# capstone_electrical_circuit_rev3.net
KiCad netlist of a schematic drawn in EAGLE
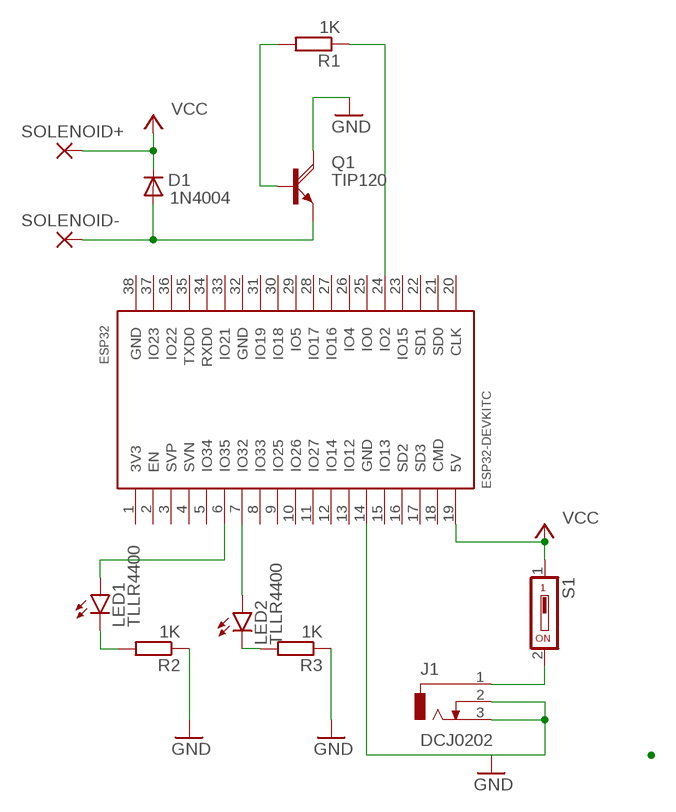
[diagram p0: schematic, sheet 1]

(export (version "E")
  (design (tool "Eeschema 10.0.6"))
  (components
    (comp (ref "D1")
      (value "1N4004")
      (footprint "eagle-import:DO41-10")
      (libsource (lib "eagle-import") (part "1N4004"))
    )
    (comp (ref "ESP32")
      (value "ESP32DEVKITC")
      (footprint "eagle-import:ESP32-DEVKITC")
      (libsource (lib "eagle-import") (part "ESP32DEVKITC"))
    )
    (comp (ref "J1")
      (value "DCJ0202")
      (footprint "eagle-import:DCJ0202")
      (libsource (lib "eagle-import") (part "DCJ0202"))
    )
    (comp (ref "LED1")
      (value "TLLR4400")
      (footprint "eagle-import:LED3MM")
      (fields (field (name "MF") "VISHAY SEMICONDUCTOR"))
      (libsource (lib "eagle-import") (part "TLLR4400"))
    )
    (comp (ref "LED2")
      (value "TLLR4400")
      (footprint "eagle-import:LED3MM")
      (fields (field (name "MF") "VISHAY SEMICONDUCTOR"))
      (libsource (lib "eagle-import") (part "TLLR4400"))
    )
    (comp (ref "Q1")
      (value "TIP120")
      (footprint "eagle-import:TO220AH")
      (libsource (lib "eagle-import") (part "TIP120"))
    )
    (comp (ref "R1")
      (value "1K")
      (footprint "eagle-import:0207_10")
      (libsource (lib "eagle-import") (part "R-EU_0207/10"))
    )
    (comp (ref "R2")
      (value "1K")
      (footprint "eagle-import:0207_10")
      (libsource (lib "eagle-import") (part "R-EU_0207/10"))
    )
    (comp (ref "R3")
      (value "1K")
      (footprint "eagle-import:0207_10")
      (libsource (lib "eagle-import") (part "R-EU_0207/10"))
    )
    (comp (ref "S1")
      (value "SD4-01")
      (footprint "eagle-import:SD4-01")
      (libsource (lib "eagle-import") (part "SD4-01"))
    )
    (comp (ref "SOLENOID+")
      (value "WIREPAD2,54/1,0")
      (footprint "eagle-import:2,54_1,0")
      (libsource (lib "eagle-import") (part "WIREPAD2,54/1,0"))
    )
    (comp (ref "SOLENOID-")
      (value "WIREPAD2,54/1,0")
      (footprint "eagle-import:2,54_1,0")
      (libsource (lib "eagle-import") (part "WIREPAD2,54/1,0"))
    )
  )
  (nets
    (net (code "1") (name "GND") (class "Default")
      (node (ref "ESP32") (pin "14") (pinfunction "GND_14") (pintype "bidirectional"))
      (node (ref "J1") (pin "2") (pinfunction "2_2") (pintype "passive"))
      (node (ref "J1") (pin "3") (pinfunction "3_3") (pintype "passive"))
      (node (ref "Q1") (pin "C") (pinfunction "C_C") (pintype "passive"))
      (node (ref "R2") (pin "1") (pinfunction "1_1") (pintype "passive"))
      (node (ref "R3") (pin "1") (pinfunction "1_1") (pintype "passive"))
    )
    (net (code "2") (name "Net-(ESP32-IO2)") (class "Default")
      (node (ref "ESP32") (pin "24") (pinfunction "IO2_24") (pintype "bidirectional"))
      (node (ref "R1") (pin "1") (pinfunction "1_1") (pintype "passive"))
    )
    (net (code "3") (name "Net-(ESP32-IO32)") (class "Default")
      (node (ref "ESP32") (pin "7") (pinfunction "IO32_7") (pintype "bidirectional"))
      (node (ref "LED2") (pin "A") (pinfunction "A_A") (pintype "passive"))
    )
    (net (code "4") (name "Net-(ESP32-IO35)") (class "Default")
      (node (ref "ESP32") (pin "6") (pinfunction "IO35_6") (pintype "bidirectional"))
      (node (ref "LED1") (pin "A") (pinfunction "A_A") (pintype "passive"))
    )
    (net (code "5") (name "Net-(J1-Pad1)") (class "Default")
      (node (ref "J1") (pin "1") (pinfunction "1_1") (pintype "passive"))
      (node (ref "S1") (pin "2") (pinfunction "2_2") (pintype "passive"))
    )
    (net (code "6") (name "Net-(LED1-C)") (class "Default")
      (node (ref "LED1") (pin "K") (pinfunction "C_K") (pintype "passive"))
      (node (ref "R2") (pin "2") (pinfunction "2_2") (pintype "passive"))
    )
    (net (code "7") (name "Net-(LED2-C)") (class "Default")
      (node (ref "LED2") (pin "K") (pinfunction "C_K") (pintype "passive"))
      (node (ref "R3") (pin "2") (pinfunction "2_2") (pintype "passive"))
    )
    (net (code "8") (name "Net-(Q1-PadB)") (class "Default")
      (node (ref "Q1") (pin "B") (pinfunction "B_B") (pintype "passive"))
      (node (ref "R1") (pin "2") (pinfunction "2_2") (pintype "passive"))
    )
    (net (code "9") (name "Net-(SOLENOID--P)") (class "Default")
      (node (ref "D1") (pin "A") (pinfunction "A_A") (pintype "passive"))
      (node (ref "Q1") (pin "E") (pinfunction "E_E") (pintype "passive"))
      (node (ref "SOLENOID-") (pin "1") (pinfunction "P_1") (pintype "passive"))
    )
    (net (code "10") (name "VCC") (class "Default")
      (node (ref "D1") (pin "C") (pinfunction "C_C") (pintype "passive"))
      (node (ref "ESP32") (pin "19") (pinfunction "5V_19") (pintype "bidirectional"))
      (node (ref "S1") (pin "1") (pinfunction "1_1") (pintype "passive"))
      (node (ref "SOLENOID+") (pin "1") (pinfunction "P_1") (pintype "passive"))
    )
    (net (code "11") (name "unconnected-(ESP32-3V3-Pad1)") (class "Default")
      (node (ref "ESP32") (pin "1") (pinfunction "3V3_1") (pintype "bidirectional"))
    )
    (net (code "12") (name "unconnected-(ESP32-CLK-Pad20)") (class "Default")
      (node (ref "ESP32") (pin "20") (pinfunction "CLK_20") (pintype "bidirectional"))
    )
    (net (code "13") (name "unconnected-(ESP32-CMD-Pad18)") (class "Default")
      (node (ref "ESP32") (pin "18") (pinfunction "CMD_18") (pintype "bidirectional"))
    )
    (net (code "14") (name "unconnected-(ESP32-EN-Pad2)") (class "Default")
      (node (ref "ESP32") (pin "2") (pinfunction "EN_2") (pintype "bidirectional"))
    )
    (net (code "15") (name "unconnected-(ESP32-GND-Pad32)") (class "Default")
      (node (ref "ESP32") (pin "32") (pinfunction "GND_32") (pintype "bidirectional"))
    )
    (net (code "16") (name "unconnected-(ESP32-GND-Pad38)") (class "Default")
      (node (ref "ESP32") (pin "38") (pinfunction "GND_38") (pintype "bidirectional"))
    )
    (net (code "17") (name "unconnected-(ESP32-IO0-Pad25)") (class "Default")
      (node (ref "ESP32") (pin "25") (pinfunction "IO0_25") (pintype "bidirectional"))
    )
    (net (code "18") (name "unconnected-(ESP32-IO4-Pad26)") (class "Default")
      (node (ref "ESP32") (pin "26") (pinfunction "IO4_26") (pintype "bidirectional"))
    )
    (net (code "19") (name "unconnected-(ESP32-IO5-Pad29)") (class "Default")
      (node (ref "ESP32") (pin "29") (pinfunction "IO5_29") (pintype "bidirectional"))
    )
    (net (code "20") (name "unconnected-(ESP32-IO12-Pad13)") (class "Default")
      (node (ref "ESP32") (pin "13") (pinfunction "IO12_13") (pintype "bidirectional"))
    )
    (net (code "21") (name "unconnected-(ESP32-IO13-Pad15)") (class "Default")
      (node (ref "ESP32") (pin "15") (pinfunction "IO13_15") (pintype "bidirectional"))
    )
    (net (code "22") (name "unconnected-(ESP32-IO14-Pad12)") (class "Default")
      (node (ref "ESP32") (pin "12") (pinfunction "IO14_12") (pintype "bidirectional"))
    )
    (net (code "23") (name "unconnected-(ESP32-IO15-Pad23)") (class "Default")
      (node (ref "ESP32") (pin "23") (pinfunction "IO15_23") (pintype "bidirectional"))
    )
    (net (code "24") (name "unconnected-(ESP32-IO16-Pad27)") (class "Default")
      (node (ref "ESP32") (pin "27") (pinfunction "IO16_27") (pintype "bidirectional"))
    )
    (net (code "25") (name "unconnected-(ESP32-IO17-Pad28)") (class "Default")
      (node (ref "ESP32") (pin "28") (pinfunction "IO17_28") (pintype "bidirectional"))
    )
    (net (code "26") (name "unconnected-(ESP32-IO18-Pad30)") (class "Default")
      (node (ref "ESP32") (pin "30") (pinfunction "IO18_30") (pintype "bidirectional"))
    )
    (net (code "27") (name "unconnected-(ESP32-IO19-Pad31)") (class "Default")
      (node (ref "ESP32") (pin "31") (pinfunction "IO19_31") (pintype "bidirectional"))
    )
    (net (code "28") (name "unconnected-(ESP32-IO21-Pad33)") (class "Default")
      (node (ref "ESP32") (pin "33") (pinfunction "IO21_33") (pintype "bidirectional"))
    )
    (net (code "29") (name "unconnected-(ESP32-IO22-Pad36)") (class "Default")
      (node (ref "ESP32") (pin "36") (pinfunction "IO22_36") (pintype "bidirectional"))
    )
    (net (code "30") (name "unconnected-(ESP32-IO23-Pad37)") (class "Default")
      (node (ref "ESP32") (pin "37") (pinfunction "IO23_37") (pintype "bidirectional"))
    )
    (net (code "31") (name "unconnected-(ESP32-IO25-Pad9)") (class "Default")
      (node (ref "ESP32") (pin "9") (pinfunction "IO25_9") (pintype "bidirectional"))
    )
    (net (code "32") (name "unconnected-(ESP32-IO26-Pad10)") (class "Default")
      (node (ref "ESP32") (pin "10") (pinfunction "IO26_10") (pintype "bidirectional"))
    )
    (net (code "33") (name "unconnected-(ESP32-IO27-Pad11)") (class "Default")
      (node (ref "ESP32") (pin "11") (pinfunction "IO27_11") (pintype "bidirectional"))
    )
    (net (code "34") (name "unconnected-(ESP32-IO33-Pad8)") (class "Default")
      (node (ref "ESP32") (pin "8") (pinfunction "IO33_8") (pintype "bidirectional"))
    )
    (net (code "35") (name "unconnected-(ESP32-IO34-Pad5)") (class "Default")
      (node (ref "ESP32") (pin "5") (pinfunction "IO34_5") (pintype "bidirectional"))
    )
    (net (code "36") (name "unconnected-(ESP32-RXD0-Pad34)") (class "Default")
      (node (ref "ESP32") (pin "34") (pinfunction "RXD0_34") (pintype "bidirectional"))
    )
    (net (code "37") (name "unconnected-(ESP32-SD0-Pad21)") (class "Default")
      (node (ref "ESP32") (pin "21") (pinfunction "SD0_21") (pintype "bidirectional"))
    )
    (net (code "38") (name "unconnected-(ESP32-SD1-Pad22)") (class "Default")
      (node (ref "ESP32") (pin "22") (pinfunction "SD1_22") (pintype "bidirectional"))
    )
    (net (code "39") (name "unconnected-(ESP32-SD2-Pad16)") (class "Default")
      (node (ref "ESP32") (pin "16") (pinfunction "SD2_16") (pintype "bidirectional"))
    )
    (net (code "40") (name "unconnected-(ESP32-SD3-Pad17)") (class "Default")
      (node (ref "ESP32") (pin "17") (pinfunction "SD3_17") (pintype "bidirectional"))
    )
    (net (code "41") (name "unconnected-(ESP32-SVN-Pad4)") (class "Default")
      (node (ref "ESP32") (pin "4") (pinfunction "SVN_4") (pintype "bidirectional"))
    )
    (net (code "42") (name "unconnected-(ESP32-SVP-Pad3)") (class "Default")
      (node (ref "ESP32") (pin "3") (pinfunction "SVP_3") (pintype "bidirectional"))
    )
    (net (code "43") (name "unconnected-(ESP32-TXD0-Pad35)") (class "Default")
      (node (ref "ESP32") (pin "35") (pinfunction "TXD0_35") (pintype "bidirectional"))
    )
  )
)
